# MZ.net
KiCad netlist of a schematic drawn in Altium Designer
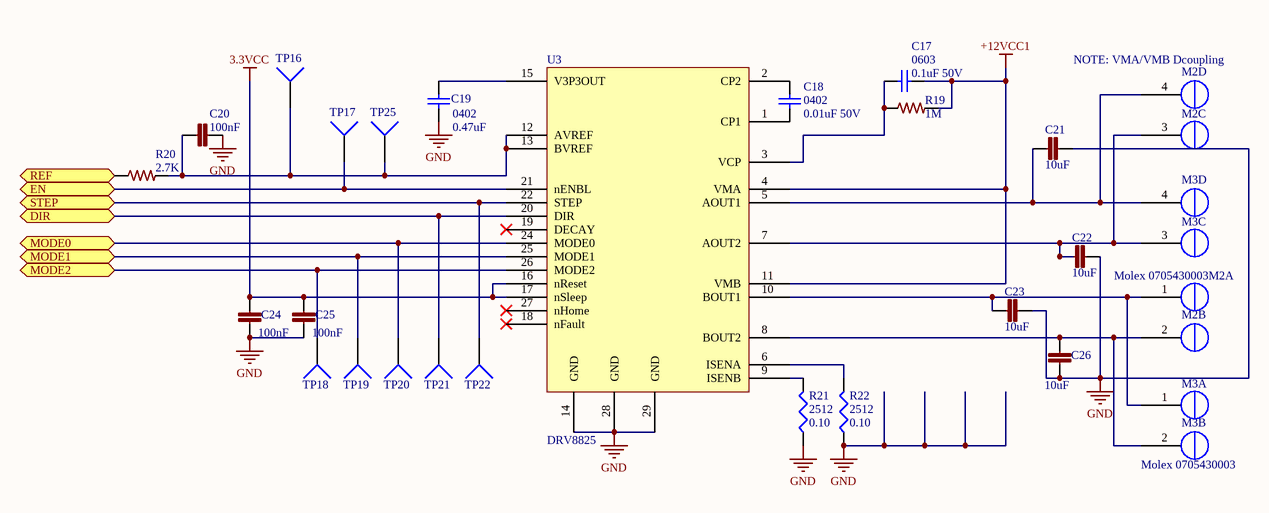
[diagram p0: MZ.SchDoc]

(export (version "E")
  (design (tool "Eeschema 10.0.6"))
  (components
    (comp (ref "C17")
      (value "0603")
      (footprint "1608[0603]")
      (description "Capacitor (Semiconductor SIM Model)")
      (fields (field (name "ALTIUM_VALUE") "0.1uF 50V") (field (name "PUBLISHER") "Altium Limited"))
      (libsource (lib "Miscellaneous Devices") (part "Cap Semi"))
    )
    (comp (ref "C18")
      (value "0.01uF 50V")
      (footprint "C0402")
      (description "CAP CER 10000PF 50V X7R 0402")
      (fields
        (field (name "MFR PART #") "GRM155R71H103JA88D")
        (field (name "MFR") "Murata")
        (field (name "PACKAGEREFERENCE") "0402")
        (field (name "PUBLISHER") "Ultimachine")
      )
      (libsource (lib "Tigershark3D") (part "GRM155R71H103JA88D"))
    )
    (comp (ref "C19")
      (value "0.47uF")
      (footprint "C0402")
      (description "0.47uF 6.3v C0402 - GRM155R60J474KE19D")
      (fields
        (field (name "MFR PART #") "GRM155R60J474KE19D")
        (field (name "MFR") "Murata")
        (field (name "PACKAGEREFERENCE") "0402")
        (field (name "PUBLISHER") "Ultimachine")
      )
      (libsource (lib "Tigershark3D") (part "GRM155R60J474KE19D"))
    )
    (comp (ref "C20")
      (value "100nF")
      (footprint "C0402")
      (description "CAP CER 0402 100nF 16V 10% X7R")
      (fields
        (field (name "MANUFACTURERPARTNUMBER") "GRM155R71C104KA88D")
        (field (name "PUBLISHER") "UltiMachine")
      )
      (libsource (lib "") (part "GRM155R71C104KA88D_1"))
    )
    (comp (ref "C21")
      (value "10uF")
      (footprint "C0603")
      (description "CAP CER 0603 1uF 10V Y5V")
      (fields
        (field (name "MANUFACTURERPARTNUMBER") "CC0603ZRY5V6BB105")
        (field (name "PUBLISHER") "UltiMachine")
      )
      (libsource (lib "Tigershark3D") (part "CC0603ZRY5V6BB105"))
    )
    (comp (ref "C22")
      (value "10uF")
      (footprint "C0603")
      (description "CAP CER 0603 1uF 10V Y5V")
      (fields
        (field (name "MANUFACTURERPARTNUMBER") "CC0603ZRY5V6BB105")
        (field (name "PUBLISHER") "UltiMachine")
      )
      (libsource (lib "Tigershark3D") (part "CC0603ZRY5V6BB105"))
    )
    (comp (ref "C23")
      (value "10uF")
      (footprint "C0603")
      (description "CAP CER 0603 1uF 10V Y5V")
      (fields
        (field (name "MANUFACTURERPARTNUMBER") "CC0603ZRY5V6BB105")
        (field (name "PUBLISHER") "UltiMachine")
      )
      (libsource (lib "Tigershark3D") (part "CC0603ZRY5V6BB105"))
    )
    (comp (ref "C24")
      (value "100nF")
      (footprint "C0402")
      (description "CAP CER 0402 100nF 16V 10% X7R")
      (fields
        (field (name "MANUFACTURERPARTNUMBER") "GRM155R71C104KA88D")
        (field (name "PUBLISHER") "UltiMachine")
      )
      (libsource (lib "3Delight") (part "GRM155R71C104KA88D"))
    )
    (comp (ref "C25")
      (value "100nF")
      (footprint "C0402")
      (description "CAP CER 0402 100nF 16V 10% X7R")
      (fields
        (field (name "MANUFACTURERPARTNUMBER") "GRM155R71C104KA88D")
        (field (name "PUBLISHER") "UltiMachine")
      )
      (libsource (lib "3Delight") (part "GRM155R71C104KA88D"))
    )
    (comp (ref "C26")
      (value "10uF")
      (footprint "C0603")
      (description "CAP CER 0603 1uF 10V Y5V")
      (fields
        (field (name "MANUFACTURERPARTNUMBER") "CC0603ZRY5V6BB105")
        (field (name "PUBLISHER") "UltiMachine")
      )
      (libsource (lib "") (part "CC0603ZRY5V6BB105_1"))
    )
    (comp (ref "M2")
      (value "Molex 0705430003")
      (footprint "4POL254")
      (description "Molex 4 Pin Clip Connector")
      (libsource (lib "ZMBo Schematic Library") (part "Molex 0705430003 Alt"))
    )
    (comp (ref "M3")
      (value "Molex 0705430003")
      (footprint "4POL254")
      (description "Molex 4 Pin Clip Connector")
      (libsource (lib "ZMBo Schematic Library") (part "Molex 0705430003 Alt"))
    )
    (comp (ref "R19")
      (value "1M")
      (footprint "R0402")
      (description "RES 0402 1M 100mW 5%")
      (fields (field (name "MANUFACTURERPARTNUMBER") "ERJ2GEJ105X") (field (name "PUBLISHER") "UltiMachine"))
      (libsource (lib "Tigershark3D") (part "ERJ2GEJ105X"))
    )
    (comp (ref "R20")
      (value "2.7K")
      (footprint "R0402")
      (description "RES SMD 2.7K OHM 1% 1/10W 0402")
      (fields
        (field (name "MANUFACTURER") "Panasonic")
        (field (name "MANUFACTURERPARTNUMBER") "ERJ2GEJ105X")
        (field (name "PUBLISHER") "Adam")
      )
      (libsource (lib "Tigershark3D") (part "ERJ-2RKF2701X"))
    )
    (comp (ref "R21")
      (value "2512")
      (footprint "2512R-0.55")
      (description "RES SMD 0.1 OHM 1% 2W 2512")
      (fields (field (name "MFR") "Stackpole ELectronics Inc") (field (name "ALTIUM_VALUE") "0.10"))
      (libsource (lib "Tigershark3D") (part "CSRN2512FTR100"))
    )
    (comp (ref "R22")
      (value "2512")
      (footprint "2512R-0.55")
      (description "RES SMD 0.1 OHM 1% 2W 2512")
      (fields (field (name "MFR") "Stackpole ELectronics Inc") (field (name "ALTIUM_VALUE") "0.10"))
      (libsource (lib "Tigershark3D") (part "CSRN2512FTR100"))
    )
    (comp (ref "TP16")
      (value "TP4")
      (footprint "TP-2")
      (description "Socket")
      (fields (field (name "PUBLISHER") "Altium Limited"))
      (libsource (lib "ZMBo Schematic Library") (part "Socket"))
    )
    (comp (ref "TP17")
      (value "TP4")
      (footprint "TP-2")
      (description "Socket")
      (fields (field (name "PUBLISHER") "Altium Limited"))
      (libsource (lib "ZMBo Schematic Library") (part "Socket"))
    )
    (comp (ref "TP18")
      (value "TP4")
      (footprint "TP-2")
      (description "Socket")
      (fields (field (name "PUBLISHER") "Altium Limited"))
      (libsource (lib "ZMBo Schematic Library") (part "Socket"))
    )
    (comp (ref "TP19")
      (value "TP4")
      (footprint "TP-2")
      (description "Socket")
      (fields (field (name "PUBLISHER") "Altium Limited"))
      (libsource (lib "ZMBo Schematic Library") (part "Socket"))
    )
    (comp (ref "TP20")
      (value "TP4")
      (footprint "TP-2")
      (description "Socket")
      (fields (field (name "PUBLISHER") "Altium Limited"))
      (libsource (lib "ZMBo Schematic Library") (part "Socket"))
    )
    (comp (ref "TP21")
      (value "TP4")
      (footprint "TP-2")
      (description "Socket")
      (fields (field (name "PUBLISHER") "Altium Limited"))
      (libsource (lib "ZMBo Schematic Library") (part "Socket"))
    )
    (comp (ref "TP22")
      (value "TP4")
      (footprint "TP-2")
      (description "Socket")
      (fields (field (name "PUBLISHER") "Altium Limited"))
      (libsource (lib "ZMBo Schematic Library") (part "Socket"))
    )
    (comp (ref "TP25")
      (value "TP4")
      (footprint "TP-2")
      (description "Socket")
      (fields (field (name "PUBLISHER") "Altium Limited"))
      (libsource (lib "ZMBo Schematic Library") (part "Socket"))
    )
    (comp (ref "U3")
      (value "DRV8825")
      (footprint "DRV8825PWPR")
      (description "DRV8825 Ti Stepper Driver")
      (fields (field (name "PART NUMBER") "DRV8825PWPR") (field (name "VOLTAGE") "8.2-45VDC"))
      (libsource (lib "Tigershark3D") (part "DRV8825"))
    )
  )
  (nets
    (net (code "1") (name "+12VCC1") (class "Default")
      (node (ref "C17") (pin "1") (pinfunction "1_1") (pintype "passive"))
      (node (ref "R19") (pin "2") (pinfunction "2_2") (pintype "passive"))
      (node (ref "U3") (pin "11") (pinfunction "VMB_11") (pintype "passive"))
      (node (ref "U3") (pin "4") (pinfunction "VMA_4") (pintype "passive"))
    )
    (net (code "2") (name "/DIR") (class "Default")
      (node (ref "TP21") (pin "1") (pinfunction "1_1") (pintype "passive"))
      (node (ref "U3") (pin "20") (pinfunction "DIR_20") (pintype "passive"))
    )
    (net (code "3") (name "/EN") (class "Default")
      (node (ref "TP17") (pin "1") (pinfunction "1_1") (pintype "passive"))
      (node (ref "U3") (pin "21") (pinfunction "nENBL_21") (pintype "passive"))
    )
    (net (code "4") (name "/MODE0") (class "Default")
      (node (ref "TP20") (pin "1") (pinfunction "1_1") (pintype "passive"))
      (node (ref "U3") (pin "24") (pinfunction "MODE0_24") (pintype "passive"))
    )
    (net (code "5") (name "/MODE1") (class "Default")
      (node (ref "TP19") (pin "1") (pinfunction "1_1") (pintype "passive"))
      (node (ref "U3") (pin "25") (pinfunction "MODE1_25") (pintype "passive"))
    )
    (net (code "6") (name "/MODE2") (class "Default")
      (node (ref "TP18") (pin "1") (pinfunction "1_1") (pintype "passive"))
      (node (ref "U3") (pin "26") (pinfunction "MODE2_26") (pintype "passive"))
    )
    (net (code "7") (name "/REF") (class "Default")
      (node (ref "R20") (pin "1") (pinfunction "1_1") (pintype "passive"))
    )
    (net (code "8") (name "/STEP") (class "Default")
      (node (ref "TP22") (pin "1") (pinfunction "1_1") (pintype "passive"))
      (node (ref "U3") (pin "22") (pinfunction "STEP_22") (pintype "passive"))
    )
    (net (code "9") (name "3.3VCC") (class "Default")
      (node (ref "C24") (pin "1") (pinfunction "1_1") (pintype "passive"))
      (node (ref "C25") (pin "1") (pinfunction "1_1") (pintype "passive"))
      (node (ref "U3") (pin "16") (pinfunction "nReset_16") (pintype "passive"))
      (node (ref "U3") (pin "17") (pinfunction "nSleep_17") (pintype "passive"))
    )
    (net (code "10") (name "GND") (class "Default")
      (node (ref "C19") (pin "1") (pinfunction "1_1") (pintype "passive"))
      (node (ref "C20") (pin "2") (pinfunction "2_2") (pintype "passive"))
      (node (ref "C21") (pin "2") (pinfunction "2_2") (pintype "passive"))
      (node (ref "C22") (pin "2") (pinfunction "2_2") (pintype "passive"))
      (node (ref "C23") (pin "2") (pinfunction "2_2") (pintype "passive"))
      (node (ref "C24") (pin "2") (pinfunction "2_2") (pintype "passive"))
      (node (ref "C25") (pin "2") (pinfunction "2_2") (pintype "passive"))
      (node (ref "C26") (pin "2") (pinfunction "2_2") (pintype "passive"))
      (node (ref "R21") (pin "1") (pinfunction "1_1") (pintype "passive"))
      (node (ref "R22") (pin "1") (pinfunction "1_1") (pintype "passive"))
      (node (ref "U3") (pin "14") (pinfunction "GND_14") (pintype "passive"))
      (node (ref "U3") (pin "28") (pinfunction "GND_28") (pintype "passive"))
      (node (ref "U3") (pin "29") (pinfunction "GND_29") (pintype "passive"))
    )
    (net (code "11") (name "Net-(M2A-OUT2B)") (class "Default")
      (node (ref "C23") (pin "1") (pinfunction "1_1") (pintype "passive"))
      (node (ref "M2") (pin "1") (pinfunction "OUT2B_1") (pintype "passive"))
      (node (ref "M3") (pin "1") (pinfunction "OUT2B_1") (pintype "passive"))
      (node (ref "U3") (pin "10") (pinfunction "BOUT1_10") (pintype "passive"))
    )
    (net (code "12") (name "Net-(M2B-OUT2A)") (class "Default")
      (node (ref "C26") (pin "1") (pinfunction "1_1") (pintype "passive"))
      (node (ref "M2") (pin "2") (pinfunction "OUT2A_2") (pintype "passive"))
      (node (ref "M3") (pin "2") (pinfunction "OUT2A_2") (pintype "passive"))
      (node (ref "U3") (pin "8") (pinfunction "BOUT2_8") (pintype "passive"))
    )
    (net (code "13") (name "Net-(M2C-OUT1A)") (class "Default")
      (node (ref "C22") (pin "1") (pinfunction "1_1") (pintype "passive"))
      (node (ref "M2") (pin "3") (pinfunction "OUT1A_3") (pintype "passive"))
      (node (ref "M3") (pin "3") (pinfunction "OUT1A_3") (pintype "passive"))
      (node (ref "U3") (pin "7") (pinfunction "AOUT2_7") (pintype "passive"))
    )
    (net (code "14") (name "Net-(M2D-OUT1B)") (class "Default")
      (node (ref "C21") (pin "1") (pinfunction "1_1") (pintype "passive"))
      (node (ref "M2") (pin "4") (pinfunction "OUT1B_4") (pintype "passive"))
      (node (ref "M3") (pin "4") (pinfunction "OUT1B_4") (pintype "passive"))
      (node (ref "U3") (pin "5") (pinfunction "AOUT1_5") (pintype "passive"))
    )
    (net (code "15") (name "Net-(U3-AVREF)") (class "Default")
      (node (ref "C20") (pin "1") (pinfunction "1_1") (pintype "passive"))
      (node (ref "R20") (pin "2") (pinfunction "2_2") (pintype "passive"))
      (node (ref "TP16") (pin "1") (pinfunction "1_1") (pintype "passive"))
      (node (ref "TP25") (pin "1") (pinfunction "1_1") (pintype "passive"))
      (node (ref "U3") (pin "12") (pinfunction "AVREF_12") (pintype "passive"))
      (node (ref "U3") (pin "13") (pinfunction "BVREF_13") (pintype "passive"))
    )
    (net (code "16") (name "Net-(U3-CP1)") (class "Default")
      (node (ref "C18") (pin "1") (pinfunction "1_1") (pintype "passive"))
      (node (ref "U3") (pin "1") (pinfunction "CP1_1") (pintype "passive"))
    )
    (net (code "17") (name "Net-(U3-CP2)") (class "Default")
      (node (ref "C18") (pin "2") (pinfunction "2_2") (pintype "passive"))
      (node (ref "U3") (pin "2") (pinfunction "CP2_2") (pintype "passive"))
    )
    (net (code "18") (name "Net-(U3-ISENA)") (class "Default")
      (node (ref "R22") (pin "2") (pinfunction "2_2") (pintype "passive"))
      (node (ref "U3") (pin "6") (pinfunction "ISENA_6") (pintype "passive"))
    )
    (net (code "19") (name "Net-(U3-ISENB)") (class "Default")
      (node (ref "R21") (pin "2") (pinfunction "2_2") (pintype "passive"))
      (node (ref "U3") (pin "9") (pinfunction "ISENB_9") (pintype "passive"))
    )
    (net (code "20") (name "Net-(U3-V3P3OUT)") (class "Default")
      (node (ref "C19") (pin "2") (pinfunction "2_2") (pintype "passive"))
      (node (ref "U3") (pin "15") (pinfunction "V3P3OUT_15") (pintype "passive"))
    )
    (net (code "21") (name "Net-(U3-VCP)") (class "Default")
      (node (ref "C17") (pin "2") (pinfunction "2_2") (pintype "passive"))
      (node (ref "R19") (pin "1") (pinfunction "1_1") (pintype "passive"))
      (node (ref "U3") (pin "3") (pinfunction "VCP_3") (pintype "passive"))
    )
    (net (code "22") (name "unconnected-(U3-DECAY-Pad19)") (class "Default")
      (node (ref "U3") (pin "19") (pinfunction "DECAY_19") (pintype "passive+no_connect"))
    )
    (net (code "23") (name "unconnected-(U3-NC-Pad23)") (class "Default")
      (node (ref "U3") (pin "23") (pinfunction "NC_23") (pintype "passive"))
    )
    (net (code "24") (name "unconnected-(U3-nFault-Pad18)") (class "Default")
      (node (ref "U3") (pin "18") (pinfunction "nFault_18") (pintype "passive+no_connect"))
    )
    (net (code "25") (name "unconnected-(U3-nHome-Pad27)") (class "Default")
      (node (ref "U3") (pin "27") (pinfunction "nHome_27") (pintype "passive+no_connect"))
    )
  )
)
